# Schematic.net
KiCad netlist of a schematic drawn in EAGLE
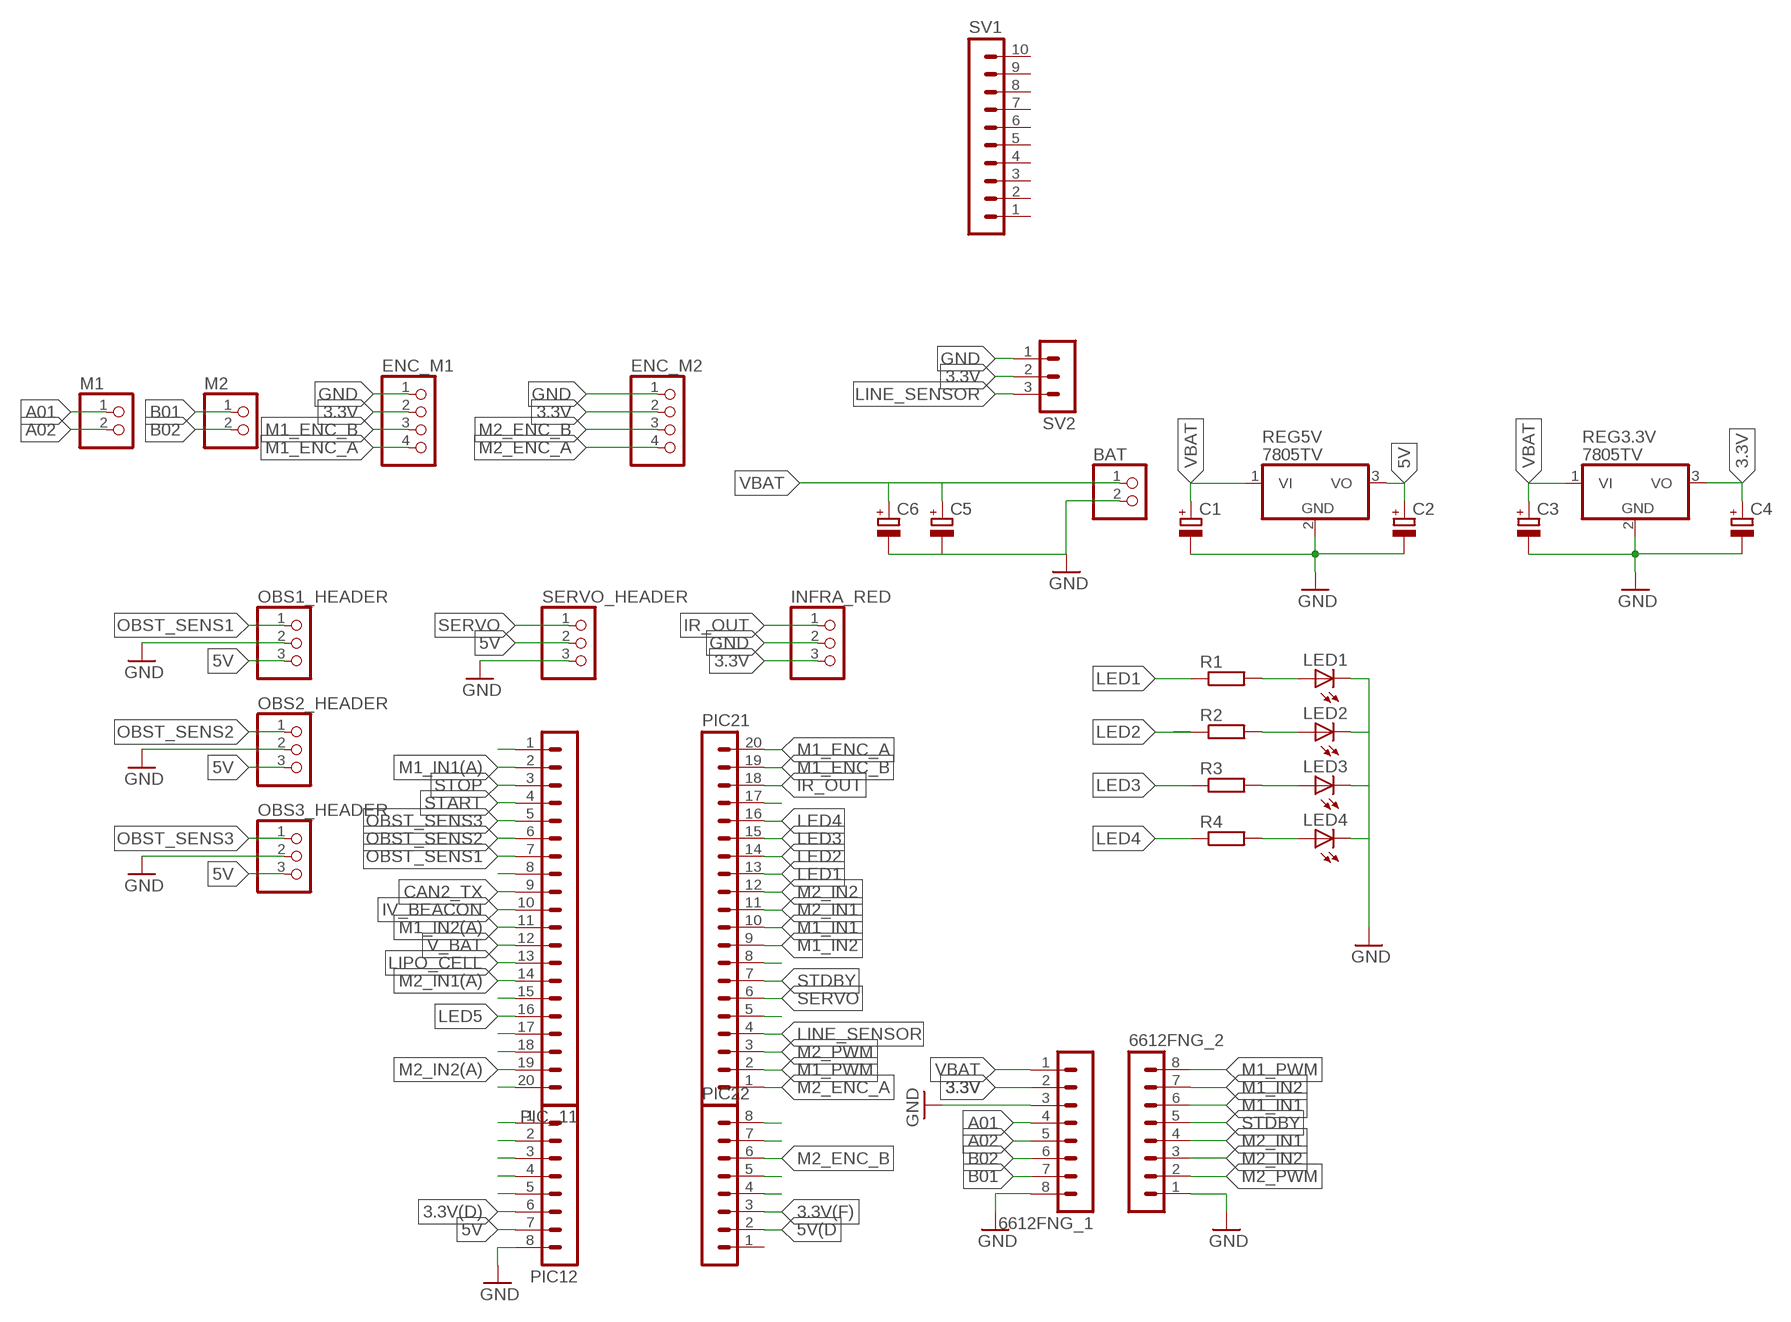
[diagram p0: schematic, sheet 1]

(export (version "E")
  (design (tool "Eeschema 10.0.6"))
  (components
    (comp (ref "6612FNG_1")
      (value "MA08-1")
      (footprint "eagle-import:MA08-1")
      (libsource (lib "eagle-import") (part "MA08-1"))
    )
    (comp (ref "6612FNG_2")
      (value "MA08-1")
      (footprint "eagle-import:MA08-1")
      (libsource (lib "eagle-import") (part "MA08-1"))
    )
    (comp (ref "BAT")
      (value "PINHD-1X2")
      (footprint "eagle-import:1X02")
      (libsource (lib "eagle-import") (part "PINHD-1X2"))
    )
    (comp (ref "C1")
      (value "CPOL-EUE2,5-6E")
      (footprint "eagle-import:E2,5-6E")
      (libsource (lib "eagle-import") (part "CPOL-EUE2,5-6E"))
    )
    (comp (ref "C2")
      (value "CPOL-EUE2,5-6E")
      (footprint "eagle-import:E2,5-6E")
      (libsource (lib "eagle-import") (part "CPOL-EUE2,5-6E"))
    )
    (comp (ref "C3")
      (value "CPOL-EUE2,5-6E")
      (footprint "eagle-import:E2,5-6E")
      (libsource (lib "eagle-import") (part "CPOL-EUE2,5-6E"))
    )
    (comp (ref "C4")
      (value "CPOL-EUE2,5-6E")
      (footprint "eagle-import:E2,5-6E")
      (libsource (lib "eagle-import") (part "CPOL-EUE2,5-6E"))
    )
    (comp (ref "C5")
      (value "CPOL-EUE2,5-6E")
      (footprint "eagle-import:E2,5-6E")
      (libsource (lib "eagle-import") (part "CPOL-EUE2,5-6E"))
    )
    (comp (ref "C6")
      (value "CPOL-EUE2,5-6E")
      (footprint "eagle-import:E2,5-6E")
      (libsource (lib "eagle-import") (part "CPOL-EUE2,5-6E"))
    )
    (comp (ref "ENC_M1")
      (value "PINHD-1X4")
      (footprint "eagle-import:1X04")
      (libsource (lib "eagle-import") (part "PINHD-1X4"))
    )
    (comp (ref "ENC_M2")
      (value "PINHD-1X4")
      (footprint "eagle-import:1X04")
      (libsource (lib "eagle-import") (part "PINHD-1X4"))
    )
    (comp (ref "INFRA_RED")
      (value "PINHD-1X3")
      (footprint "eagle-import:1X03")
      (libsource (lib "eagle-import") (part "PINHD-1X3"))
    )
    (comp (ref "LED1")
      (value "LED3MM")
      (footprint "eagle-import:LED3MM")
      (libsource (lib "eagle-import") (part "LED3MM"))
    )
    (comp (ref "LED2")
      (value "LED3MM")
      (footprint "eagle-import:LED3MM")
      (libsource (lib "eagle-import") (part "LED3MM"))
    )
    (comp (ref "LED3")
      (value "LED3MM")
      (footprint "eagle-import:LED3MM")
      (libsource (lib "eagle-import") (part "LED3MM"))
    )
    (comp (ref "LED4")
      (value "LED3MM")
      (footprint "eagle-import:LED3MM")
      (libsource (lib "eagle-import") (part "LED3MM"))
    )
    (comp (ref "M1")
      (value "PINHD-1X2")
      (footprint "eagle-import:1X02")
      (libsource (lib "eagle-import") (part "PINHD-1X2"))
    )
    (comp (ref "M2")
      (value "PINHD-1X2")
      (footprint "eagle-import:1X02")
      (libsource (lib "eagle-import") (part "PINHD-1X2"))
    )
    (comp (ref "OBS1_HEADER")
      (value "PINHD-1X3")
      (footprint "eagle-import:1X03")
      (libsource (lib "eagle-import") (part "PINHD-1X3"))
    )
    (comp (ref "OBS2_HEADER")
      (value "PINHD-1X3")
      (footprint "eagle-import:1X03")
      (libsource (lib "eagle-import") (part "PINHD-1X3"))
    )
    (comp (ref "OBS3_HEADER")
      (value "PINHD-1X3")
      (footprint "eagle-import:1X03")
      (libsource (lib "eagle-import") (part "PINHD-1X3"))
    )
    (comp (ref "PIC12")
      (value "MA08-1")
      (footprint "eagle-import:MA08-1")
      (libsource (lib "eagle-import") (part "MA08-1"))
    )
    (comp (ref "PIC21")
      (value "MA20-1")
      (footprint "eagle-import:MA20-1")
      (libsource (lib "eagle-import") (part "MA20-1"))
    )
    (comp (ref "PIC22")
      (value "MA08-1")
      (footprint "eagle-import:MA08-1")
      (libsource (lib "eagle-import") (part "MA08-1"))
    )
    (comp (ref "PIC_11")
      (value "MA20-1")
      (footprint "eagle-import:MA20-1")
      (libsource (lib "eagle-import") (part "MA20-1"))
    )
    (comp (ref "R1")
      (value "R-EU_0207/7")
      (footprint "eagle-import:0207_7")
      (libsource (lib "eagle-import") (part "R-EU_0207/7"))
    )
    (comp (ref "R2")
      (value "R-EU_0207/7")
      (footprint "eagle-import:0207_7")
      (libsource (lib "eagle-import") (part "R-EU_0207/7"))
    )
    (comp (ref "R3")
      (value "R-EU_0207/7")
      (footprint "eagle-import:0207_7")
      (libsource (lib "eagle-import") (part "R-EU_0207/7"))
    )
    (comp (ref "R4")
      (value "R-EU_0207/7")
      (footprint "eagle-import:0207_7")
      (libsource (lib "eagle-import") (part "R-EU_0207/7"))
    )
    (comp (ref "REG3.3V")
      (value "7805TV")
      (footprint "eagle-import:TO220V")
      (libsource (lib "eagle-import") (part "78TV05"))
    )
    (comp (ref "REG5V")
      (value "7805TV")
      (footprint "eagle-import:TO220V")
      (libsource (lib "eagle-import") (part "78TV05"))
    )
    (comp (ref "SERVO_HEADER")
      (value "PINHD-1X3")
      (footprint "eagle-import:1X03")
      (libsource (lib "eagle-import") (part "PINHD-1X3"))
    )
    (comp (ref "SV1")
      (value "MA10-1")
      (footprint "eagle-import:MA10-1")
      (libsource (lib "eagle-import") (part "MA10-1"))
    )
    (comp (ref "SV2")
      (value "MA03-1")
      (footprint "eagle-import:MA03-1")
      (libsource (lib "eagle-import") (part "MA03-1"))
    )
  )
  (nets
    (net (code "1") (name "3.3V") (class "Default")
      (node (ref "6612FNG_1") (pin "2") (pinfunction "2_2") (pintype "passive"))
      (node (ref "C4") (pin "+") (pinfunction "+_+") (pintype "passive"))
      (node (ref "ENC_M1") (pin "2") (pinfunction "2_2") (pintype "passive"))
      (node (ref "ENC_M2") (pin "2") (pinfunction "2_2") (pintype "passive"))
      (node (ref "INFRA_RED") (pin "3") (pinfunction "3_3") (pintype "passive"))
      (node (ref "REG3.3V") (pin "3") (pinfunction "VO_3") (pintype "passive"))
      (node (ref "SV2") (pin "2") (pinfunction "2_2") (pintype "passive"))
    )
    (net (code "2") (name "3.3V(D)") (class "Default")
      (node (ref "PIC12") (pin "6") (pinfunction "6_6") (pintype "passive"))
    )
    (net (code "3") (name "3.3V(F)") (class "Default")
      (node (ref "PIC22") (pin "3") (pinfunction "3_3") (pintype "passive"))
    )
    (net (code "4") (name "5V") (class "Default")
      (node (ref "C2") (pin "+") (pinfunction "+_+") (pintype "passive"))
      (node (ref "OBS1_HEADER") (pin "3") (pinfunction "3_3") (pintype "passive"))
      (node (ref "OBS2_HEADER") (pin "3") (pinfunction "3_3") (pintype "passive"))
      (node (ref "OBS3_HEADER") (pin "3") (pinfunction "3_3") (pintype "passive"))
      (node (ref "PIC12") (pin "7") (pinfunction "7_7") (pintype "passive"))
      (node (ref "REG5V") (pin "3") (pinfunction "VO_3") (pintype "passive"))
      (node (ref "SERVO_HEADER") (pin "2") (pinfunction "2_2") (pintype "passive"))
    )
    (net (code "5") (name "5V(D") (class "Default")
      (node (ref "PIC22") (pin "2") (pinfunction "2_2") (pintype "passive"))
    )
    (net (code "6") (name "A01") (class "Default")
      (node (ref "6612FNG_1") (pin "4") (pinfunction "4_4") (pintype "passive"))
      (node (ref "M1") (pin "1") (pinfunction "1_1") (pintype "passive"))
    )
    (net (code "7") (name "A02") (class "Default")
      (node (ref "6612FNG_1") (pin "5") (pinfunction "5_5") (pintype "passive"))
      (node (ref "M1") (pin "2") (pinfunction "2_2") (pintype "passive"))
    )
    (net (code "8") (name "B01") (class "Default")
      (node (ref "6612FNG_1") (pin "7") (pinfunction "7_7") (pintype "passive"))
      (node (ref "M2") (pin "1") (pinfunction "1_1") (pintype "passive"))
    )
    (net (code "9") (name "B02") (class "Default")
      (node (ref "6612FNG_1") (pin "6") (pinfunction "6_6") (pintype "passive"))
      (node (ref "M2") (pin "2") (pinfunction "2_2") (pintype "passive"))
    )
    (net (code "10") (name "CAN2_TX") (class "Default")
      (node (ref "PIC_11") (pin "9") (pinfunction "9_9") (pintype "passive"))
    )
    (net (code "11") (name "GND") (class "Default")
      (node (ref "6612FNG_1") (pin "3") (pinfunction "3_3") (pintype "passive"))
      (node (ref "6612FNG_1") (pin "8") (pinfunction "8_8") (pintype "passive"))
      (node (ref "6612FNG_2") (pin "1") (pinfunction "1_1") (pintype "passive"))
      (node (ref "BAT") (pin "2") (pinfunction "2_2") (pintype "passive"))
      (node (ref "C1") (pin "-") (pinfunction "-_-") (pintype "passive"))
      (node (ref "C2") (pin "-") (pinfunction "-_-") (pintype "passive"))
      (node (ref "C3") (pin "-") (pinfunction "-_-") (pintype "passive"))
      (node (ref "C4") (pin "-") (pinfunction "-_-") (pintype "passive"))
      (node (ref "C5") (pin "-") (pinfunction "-_-") (pintype "passive"))
      (node (ref "C6") (pin "-") (pinfunction "-_-") (pintype "passive"))
      (node (ref "ENC_M1") (pin "1") (pinfunction "1_1") (pintype "passive"))
      (node (ref "ENC_M2") (pin "1") (pinfunction "1_1") (pintype "passive"))
      (node (ref "INFRA_RED") (pin "2") (pinfunction "2_2") (pintype "passive"))
      (node (ref "LED1") (pin "K") (pinfunction "C_K") (pintype "passive"))
      (node (ref "LED2") (pin "K") (pinfunction "C_K") (pintype "passive"))
      (node (ref "LED3") (pin "K") (pinfunction "C_K") (pintype "passive"))
      (node (ref "LED4") (pin "K") (pinfunction "C_K") (pintype "passive"))
      (node (ref "OBS1_HEADER") (pin "2") (pinfunction "2_2") (pintype "passive"))
      (node (ref "OBS2_HEADER") (pin "2") (pinfunction "2_2") (pintype "passive"))
      (node (ref "OBS3_HEADER") (pin "2") (pinfunction "2_2") (pintype "passive"))
      (node (ref "PIC12") (pin "8") (pinfunction "8_8") (pintype "passive"))
      (node (ref "REG3.3V") (pin "2") (pinfunction "GND_2") (pintype "passive"))
      (node (ref "REG5V") (pin "2") (pinfunction "GND_2") (pintype "passive"))
      (node (ref "SERVO_HEADER") (pin "3") (pinfunction "3_3") (pintype "passive"))
      (node (ref "SV2") (pin "1") (pinfunction "1_1") (pintype "passive"))
    )
    (net (code "12") (name "IR_OUT") (class "Default")
      (node (ref "INFRA_RED") (pin "1") (pinfunction "1_1") (pintype "passive"))
      (node (ref "PIC21") (pin "18") (pinfunction "18_18") (pintype "passive"))
    )
    (net (code "13") (name "IV_BEACON") (class "Default")
      (node (ref "PIC_11") (pin "10") (pinfunction "10_10") (pintype "passive"))
    )
    (net (code "14") (name "LED1") (class "Default")
      (node (ref "PIC21") (pin "13") (pinfunction "13_13") (pintype "passive"))
      (node (ref "R1") (pin "1") (pinfunction "1_1") (pintype "passive"))
    )
    (net (code "15") (name "LED2") (class "Default")
      (node (ref "PIC21") (pin "14") (pinfunction "14_14") (pintype "passive"))
      (node (ref "R2") (pin "1") (pinfunction "1_1") (pintype "passive"))
    )
    (net (code "16") (name "LED3") (class "Default")
      (node (ref "PIC21") (pin "15") (pinfunction "15_15") (pintype "passive"))
      (node (ref "R3") (pin "1") (pinfunction "1_1") (pintype "passive"))
    )
    (net (code "17") (name "LED4") (class "Default")
      (node (ref "PIC21") (pin "16") (pinfunction "16_16") (pintype "passive"))
      (node (ref "R4") (pin "1") (pinfunction "1_1") (pintype "passive"))
    )
    (net (code "18") (name "LED5") (class "Default")
      (node (ref "PIC_11") (pin "16") (pinfunction "16_16") (pintype "passive"))
    )
    (net (code "19") (name "LINE_SENSOR") (class "Default")
      (node (ref "PIC21") (pin "4") (pinfunction "4_4") (pintype "passive"))
      (node (ref "SV2") (pin "3") (pinfunction "3_3") (pintype "passive"))
    )
    (net (code "20") (name "LIPO_CELL") (class "Default")
      (node (ref "PIC_11") (pin "13") (pinfunction "13_13") (pintype "passive"))
    )
    (net (code "21") (name "M1_ENC_A") (class "Default")
      (node (ref "ENC_M1") (pin "4") (pinfunction "4_4") (pintype "passive"))
      (node (ref "PIC21") (pin "20") (pinfunction "20_20") (pintype "passive"))
    )
    (net (code "22") (name "M1_ENC_B") (class "Default")
      (node (ref "ENC_M1") (pin "3") (pinfunction "3_3") (pintype "passive"))
      (node (ref "PIC21") (pin "19") (pinfunction "19_19") (pintype "passive"))
    )
    (net (code "23") (name "M1_IN1") (class "Default")
      (node (ref "6612FNG_2") (pin "6") (pinfunction "6_6") (pintype "passive"))
      (node (ref "PIC21") (pin "10") (pinfunction "10_10") (pintype "passive"))
    )
    (net (code "24") (name "M1_IN1(A)") (class "Default")
      (node (ref "PIC_11") (pin "2") (pinfunction "2_2") (pintype "passive"))
    )
    (net (code "25") (name "M1_IN2") (class "Default")
      (node (ref "6612FNG_2") (pin "7") (pinfunction "7_7") (pintype "passive"))
      (node (ref "PIC21") (pin "9") (pinfunction "9_9") (pintype "passive"))
    )
    (net (code "26") (name "M1_IN2(A)") (class "Default")
      (node (ref "PIC_11") (pin "11") (pinfunction "11_11") (pintype "passive"))
    )
    (net (code "27") (name "M1_PWM") (class "Default")
      (node (ref "6612FNG_2") (pin "8") (pinfunction "8_8") (pintype "passive"))
      (node (ref "PIC21") (pin "2") (pinfunction "2_2") (pintype "passive"))
    )
    (net (code "28") (name "M2_ENC_A") (class "Default")
      (node (ref "ENC_M2") (pin "4") (pinfunction "4_4") (pintype "passive"))
      (node (ref "PIC21") (pin "1") (pinfunction "1_1") (pintype "passive"))
    )
    (net (code "29") (name "M2_ENC_B") (class "Default")
      (node (ref "ENC_M2") (pin "3") (pinfunction "3_3") (pintype "passive"))
      (node (ref "PIC22") (pin "6") (pinfunction "6_6") (pintype "passive"))
    )
    (net (code "30") (name "M2_IN1") (class "Default")
      (node (ref "6612FNG_2") (pin "4") (pinfunction "4_4") (pintype "passive"))
      (node (ref "PIC21") (pin "11") (pinfunction "11_11") (pintype "passive"))
    )
    (net (code "31") (name "M2_IN1(A)") (class "Default")
      (node (ref "PIC_11") (pin "14") (pinfunction "14_14") (pintype "passive"))
    )
    (net (code "32") (name "M2_IN2") (class "Default")
      (node (ref "6612FNG_2") (pin "3") (pinfunction "3_3") (pintype "passive"))
      (node (ref "PIC21") (pin "12") (pinfunction "12_12") (pintype "passive"))
    )
    (net (code "33") (name "M2_IN2(A)") (class "Default")
      (node (ref "PIC_11") (pin "19") (pinfunction "19_19") (pintype "passive"))
    )
    (net (code "34") (name "M2_PWM") (class "Default")
      (node (ref "6612FNG_2") (pin "2") (pinfunction "2_2") (pintype "passive"))
      (node (ref "PIC21") (pin "3") (pinfunction "3_3") (pintype "passive"))
    )
    (net (code "35") (name "Net-(LED1-PadA)") (class "Default")
      (node (ref "LED1") (pin "A") (pinfunction "A_A") (pintype "passive"))
      (node (ref "R1") (pin "2") (pinfunction "2_2") (pintype "passive"))
    )
    (net (code "36") (name "Net-(LED2-PadA)") (class "Default")
      (node (ref "LED2") (pin "A") (pinfunction "A_A") (pintype "passive"))
      (node (ref "R2") (pin "2") (pinfunction "2_2") (pintype "passive"))
    )
    (net (code "37") (name "Net-(LED3-PadA)") (class "Default")
      (node (ref "LED3") (pin "A") (pinfunction "A_A") (pintype "passive"))
      (node (ref "R3") (pin "2") (pinfunction "2_2") (pintype "passive"))
    )
    (net (code "38") (name "Net-(LED4-PadA)") (class "Default")
      (node (ref "LED4") (pin "A") (pinfunction "A_A") (pintype "passive"))
      (node (ref "R4") (pin "2") (pinfunction "2_2") (pintype "passive"))
    )
    (net (code "39") (name "OBST_SENS1") (class "Default")
      (node (ref "OBS1_HEADER") (pin "1") (pinfunction "1_1") (pintype "passive"))
      (node (ref "PIC_11") (pin "7") (pinfunction "7_7") (pintype "passive"))
    )
    (net (code "40") (name "OBST_SENS2") (class "Default")
      (node (ref "OBS2_HEADER") (pin "1") (pinfunction "1_1") (pintype "passive"))
      (node (ref "PIC_11") (pin "6") (pinfunction "6_6") (pintype "passive"))
    )
    (net (code "41") (name "OBST_SENS3") (class "Default")
      (node (ref "OBS3_HEADER") (pin "1") (pinfunction "1_1") (pintype "passive"))
      (node (ref "PIC_11") (pin "5") (pinfunction "5_5") (pintype "passive"))
    )
    (net (code "42") (name "SERVO") (class "Default")
      (node (ref "PIC21") (pin "6") (pinfunction "6_6") (pintype "passive"))
      (node (ref "SERVO_HEADER") (pin "1") (pinfunction "1_1") (pintype "passive"))
    )
    (net (code "43") (name "START") (class "Default")
      (node (ref "PIC_11") (pin "4") (pinfunction "4_4") (pintype "passive"))
    )
    (net (code "44") (name "STDBY") (class "Default")
      (node (ref "6612FNG_2") (pin "5") (pinfunction "5_5") (pintype "passive"))
      (node (ref "PIC21") (pin "7") (pinfunction "7_7") (pintype "passive"))
    )
    (net (code "45") (name "STOP") (class "Default")
      (node (ref "PIC_11") (pin "3") (pinfunction "3_3") (pintype "passive"))
    )
    (net (code "46") (name "VBAT") (class "Default")
      (node (ref "6612FNG_1") (pin "1") (pinfunction "1_1") (pintype "passive"))
      (node (ref "BAT") (pin "1") (pinfunction "1_1") (pintype "passive"))
      (node (ref "C1") (pin "+") (pinfunction "+_+") (pintype "passive"))
      (node (ref "C3") (pin "+") (pinfunction "+_+") (pintype "passive"))
      (node (ref "C5") (pin "+") (pinfunction "+_+") (pintype "passive"))
      (node (ref "C6") (pin "+") (pinfunction "+_+") (pintype "passive"))
      (node (ref "REG3.3V") (pin "1") (pinfunction "VI_1") (pintype "input"))
      (node (ref "REG5V") (pin "1") (pinfunction "VI_1") (pintype "input"))
    )
    (net (code "47") (name "V_BAT") (class "Default")
      (node (ref "PIC_11") (pin "12") (pinfunction "12_12") (pintype "passive"))
    )
    (net (code "48") (name "unconnected-(PIC12-Pad1)") (class "Default")
      (node (ref "PIC12") (pin "1") (pinfunction "1_1") (pintype "passive"))
    )
    (net (code "49") (name "unconnected-(PIC12-Pad2)") (class "Default")
      (node (ref "PIC12") (pin "2") (pinfunction "2_2") (pintype "passive"))
    )
    (net (code "50") (name "unconnected-(PIC12-Pad3)") (class "Default")
      (node (ref "PIC12") (pin "3") (pinfunction "3_3") (pintype "passive"))
    )
    (net (code "51") (name "unconnected-(PIC12-Pad4)") (class "Default")
      (node (ref "PIC12") (pin "4") (pinfunction "4_4") (pintype "passive"))
    )
    (net (code "52") (name "unconnected-(PIC12-Pad5)") (class "Default")
      (node (ref "PIC12") (pin "5") (pinfunction "5_5") (pintype "passive"))
    )
    (net (code "53") (name "unconnected-(PIC21-Pad5)") (class "Default")
      (node (ref "PIC21") (pin "5") (pinfunction "5_5") (pintype "passive"))
    )
    (net (code "54") (name "unconnected-(PIC21-Pad8)") (class "Default")
      (node (ref "PIC21") (pin "8") (pinfunction "8_8") (pintype "passive"))
    )
    (net (code "55") (name "unconnected-(PIC21-Pad17)") (class "Default")
      (node (ref "PIC21") (pin "17") (pinfunction "17_17") (pintype "passive"))
    )
    (net (code "56") (name "unconnected-(PIC22-Pad1)") (class "Default")
      (node (ref "PIC22") (pin "1") (pinfunction "1_1") (pintype "passive"))
    )
    (net (code "57") (name "unconnected-(PIC22-Pad4)") (class "Default")
      (node (ref "PIC22") (pin "4") (pinfunction "4_4") (pintype "passive"))
    )
    (net (code "58") (name "unconnected-(PIC22-Pad5)") (class "Default")
      (node (ref "PIC22") (pin "5") (pinfunction "5_5") (pintype "passive"))
    )
    (net (code "59") (name "unconnected-(PIC22-Pad7)") (class "Default")
      (node (ref "PIC22") (pin "7") (pinfunction "7_7") (pintype "passive"))
    )
    (net (code "60") (name "unconnected-(PIC22-Pad8)") (class "Default")
      (node (ref "PIC22") (pin "8") (pinfunction "8_8") (pintype "passive"))
    )
    (net (code "61") (name "unconnected-(PIC_11-Pad1)") (class "Default")
      (node (ref "PIC_11") (pin "1") (pinfunction "1_1") (pintype "passive"))
    )
    (net (code "62") (name "unconnected-(PIC_11-Pad8)") (class "Default")
      (node (ref "PIC_11") (pin "8") (pinfunction "8_8") (pintype "passive"))
    )
    (net (code "63") (name "unconnected-(PIC_11-Pad15)") (class "Default")
      (node (ref "PIC_11") (pin "15") (pinfunction "15_15") (pintype "passive"))
    )
    (net (code "64") (name "unconnected-(PIC_11-Pad17)") (class "Default")
      (node (ref "PIC_11") (pin "17") (pinfunction "17_17") (pintype "passive"))
    )
    (net (code "65") (name "unconnected-(PIC_11-Pad18)") (class "Default")
      (node (ref "PIC_11") (pin "18") (pinfunction "18_18") (pintype "passive"))
    )
    (net (code "66") (name "unconnected-(PIC_11-Pad20)") (class "Default")
      (node (ref "PIC_11") (pin "20") (pinfunction "20_20") (pintype "passive"))
    )
    (net (code "67") (name "unconnected-(SV1-Pad1)") (class "Default")
      (node (ref "SV1") (pin "1") (pinfunction "1_1") (pintype "passive"))
    )
    (net (code "68") (name "unconnected-(SV1-Pad2)") (class "Default")
      (node (ref "SV1") (pin "2") (pinfunction "2_2") (pintype "passive"))
    )
    (net (code "69") (name "unconnected-(SV1-Pad3)") (class "Default")
      (node (ref "SV1") (pin "3") (pinfunction "3_3") (pintype "passive"))
    )
    (net (code "70") (name "unconnected-(SV1-Pad4)") (class "Default")
      (node (ref "SV1") (pin "4") (pinfunction "4_4") (pintype "passive"))
    )
    (net (code "71") (name "unconnected-(SV1-Pad5)") (class "Default")
      (node (ref "SV1") (pin "5") (pinfunction "5_5") (pintype "passive"))
    )
    (net (code "72") (name "unconnected-(SV1-Pad6)") (class "Default")
      (node (ref "SV1") (pin "6") (pinfunction "6_6") (pintype "passive"))
    )
    (net (code "73") (name "unconnected-(SV1-Pad7)") (class "Default")
      (node (ref "SV1") (pin "7") (pinfunction "7_7") (pintype "passive"))
    )
    (net (code "74") (name "unconnected-(SV1-Pad8)") (class "Default")
      (node (ref "SV1") (pin "8") (pinfunction "8_8") (pintype "passive"))
    )
    (net (code "75") (name "unconnected-(SV1-Pad9)") (class "Default")
      (node (ref "SV1") (pin "9") (pinfunction "9_9") (pintype "passive"))
    )
    (net (code "76") (name "unconnected-(SV1-Pad10)") (class "Default")
      (node (ref "SV1") (pin "10") (pinfunction "10_10") (pintype "passive"))
    )
  )
)
